# Jade_v1_schematics_PG3_PMIC_AXP192.net
KiCad netlist of a schematic drawn in Altium Designer
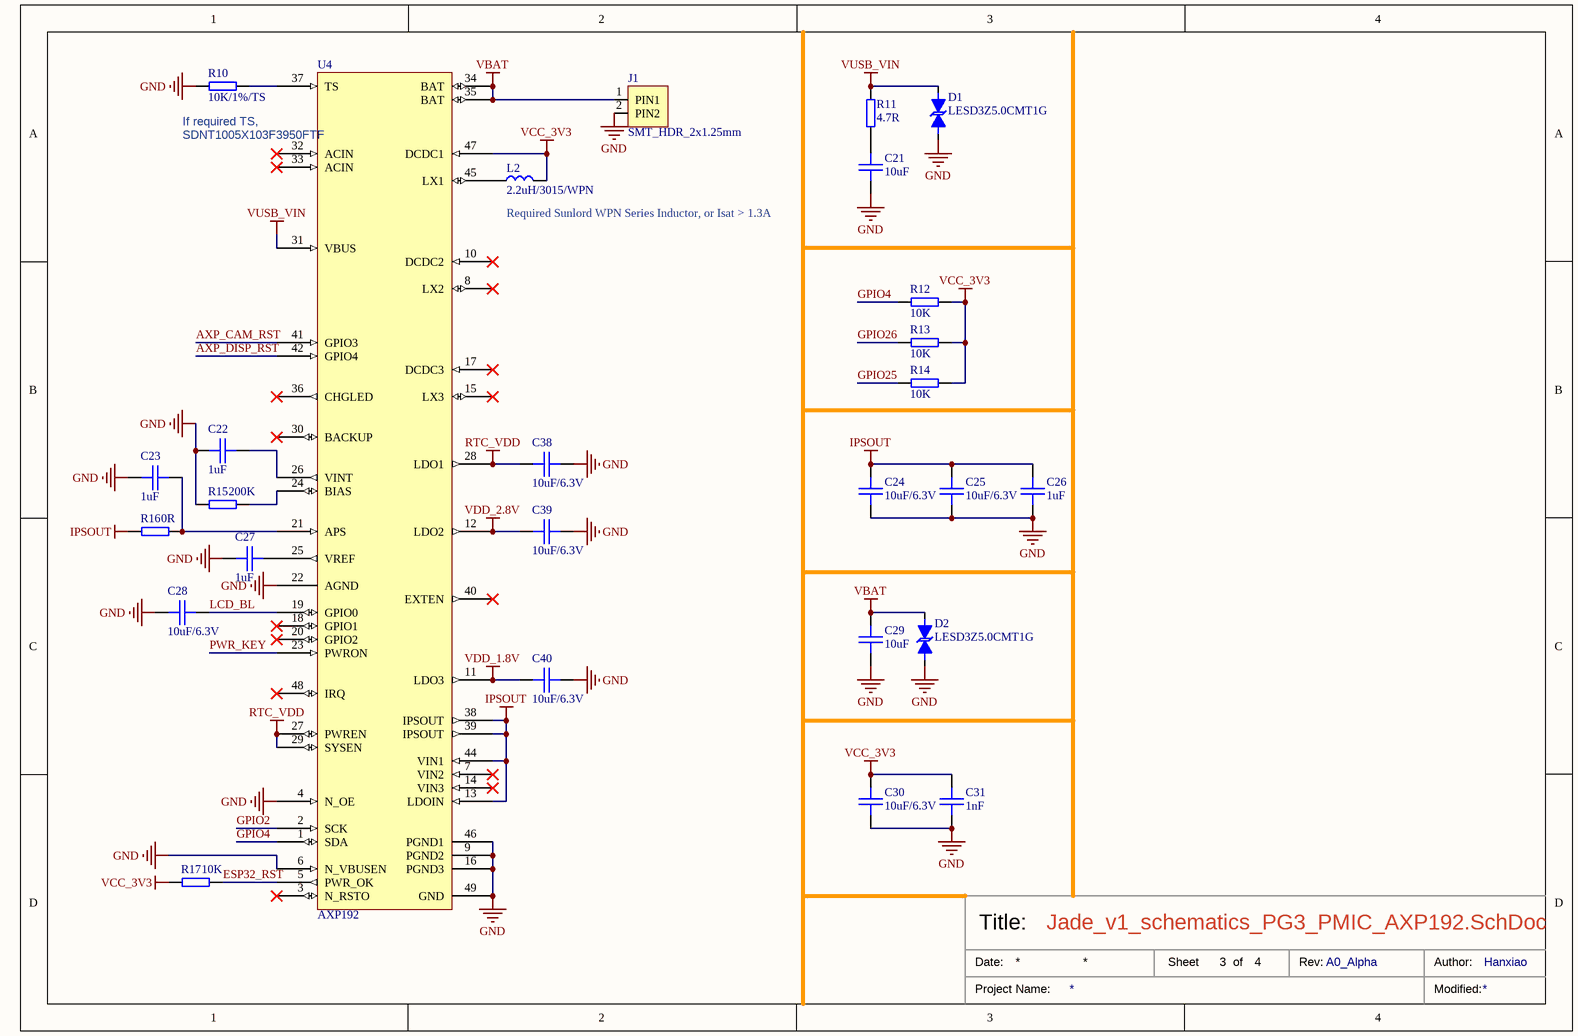
[diagram p0: Jade_v1_schematics_PG3_PMIC_AXP192.SchDoc]

(export (version "E")
  (design (tool "Eeschema 10.0.6"))
  (components
    (comp (ref "C21")
      (value "10uF")
      (footprint "SMT_C_0402")
      (description "Surface mount capacitor 0402")
      (libsource (lib "Vowstar_Basic_Device") (part "SMT_C_0402"))
    )
    (comp (ref "C22")
      (value "1uF")
      (footprint "SMT_C_0402")
      (description "Surface mount capacitor 0402")
      (libsource (lib "Vowstar_Basic_Device") (part "SMT_C_0402"))
    )
    (comp (ref "C23")
      (value "1uF")
      (footprint "SMT_C_0402")
      (description "Surface mount capacitor 0402")
      (libsource (lib "Vowstar_Basic_Device") (part "SMT_C_0402"))
    )
    (comp (ref "C24")
      (value "10uF/6.3V")
      (footprint "SMT_C_0603")
      (description "Surface mount capacitor 0603")
      (libsource (lib "Vowstar_Basic_Device") (part "SMT_C_0603"))
    )
    (comp (ref "C25")
      (value "10uF/6.3V")
      (footprint "SMT_C_0603")
      (description "Surface mount capacitor 0603")
      (libsource (lib "Vowstar_Basic_Device") (part "SMT_C_0603"))
    )
    (comp (ref "C26")
      (value "1uF")
      (footprint "SMT_C_0402")
      (description "Surface mount capacitor 0402")
      (libsource (lib "Vowstar_Basic_Device") (part "SMT_C_0402"))
    )
    (comp (ref "C27")
      (value "1uF")
      (footprint "SMT_C_0402")
      (description "Surface mount capacitor 0402")
      (libsource (lib "Vowstar_Basic_Device") (part "SMT_C_0402"))
    )
    (comp (ref "C28")
      (value "10uF/6.3V")
      (footprint "SMT_C_0603")
      (description "Surface mount capacitor 0603")
      (libsource (lib "Vowstar_Basic_Device") (part "SMT_C_0603"))
    )
    (comp (ref "C29")
      (value "10uF")
      (footprint "SMT_C_0402")
      (description "Surface mount capacitor 0402")
      (libsource (lib "Vowstar_Basic_Device") (part "SMT_C_0402"))
    )
    (comp (ref "C30")
      (value "10uF/6.3V")
      (footprint "SMT_C_0603")
      (description "Surface mount capacitor 0603")
      (libsource (lib "Vowstar_Basic_Device") (part "SMT_C_0603"))
    )
    (comp (ref "C31")
      (value "1nF")
      (footprint "SMT_C_0402")
      (description "Surface mount capacitor 0402")
      (libsource (lib "Vowstar_Basic_Device") (part "SMT_C_0402"))
    )
    (comp (ref "C38")
      (value "10uF/6.3V")
      (footprint "SMT_C_0603")
      (description "Surface mount capacitor 0603")
      (libsource (lib "Vowstar_Basic_Device") (part "SMT_C_0603"))
    )
    (comp (ref "C39")
      (value "10uF/6.3V")
      (footprint "SMT_C_0603")
      (description "Surface mount capacitor 0603")
      (libsource (lib "Vowstar_Basic_Device") (part "SMT_C_0603"))
    )
    (comp (ref "C40")
      (value "10uF/6.3V")
      (footprint "SMT_C_0603")
      (description "Surface mount capacitor 0603")
      (libsource (lib "Vowstar_Basic_Device") (part "SMT_C_0603"))
    )
    (comp (ref "D1")
      (value "LESD3Z5.0CMT1G")
      (footprint "SMT_DIODE_SOD_323")
      (description "Surface mount bidirectional TVS diode SOD-523(0603) Package")
      (libsource (lib "Vowstar_Basic_Device") (part "SMT_DIODE_TVS_B_SOD_523"))
    )
    (comp (ref "D2")
      (value "LESD3Z5.0CMT1G")
      (footprint "SMT_DIODE_SOD_323")
      (description "Surface mount bidirectional TVS diode SOD-523(0603) Package")
      (libsource (lib "Vowstar_Basic_Device") (part "SMT_DIODE_TVS_B_SOD_523"))
    )
    (comp (ref "J1")
      (value "SMT_HDR_2x1.25mm")
      (footprint "SMT_HDR_2x1.25mm")
      (description "Surface mount header 2x1.25mm")
      (libsource (lib "Vowstar_Connector") (part "SMT_HDR_2x1.25mm"))
    )
    (comp (ref "L2")
      (value "2.2uH/3015/WPN")
      (footprint "SMT_L_3.0mm")
      (description "SMT Power Inductor, 3.3x3.3x1mm")
      (libsource (lib "Vowstar_Basic_Device") (part "SMT_L_3.0mm"))
    )
    (comp (ref "R10")
      (value "10K/1%/TS")
      (footprint "SMT_R_0402")
      (description "Surface mount resistor 0402")
      (libsource (lib "Vowstar_Basic_Device") (part "SMT_R_0402"))
    )
    (comp (ref "R11")
      (value "4.7R")
      (footprint "SMT_R_0402")
      (description "Surface mount resistor 0402")
      (libsource (lib "Vowstar_Basic_Device") (part "SMT_R_0402"))
    )
    (comp (ref "R12")
      (value "10K")
      (footprint "SMT_R_0402")
      (description "Surface mount resistor 0402")
      (libsource (lib "Vowstar_Basic_Device") (part "SMT_R_0402"))
    )
    (comp (ref "R13")
      (value "10K")
      (footprint "SMT_R_0402")
      (description "Surface mount resistor 0402")
      (libsource (lib "Vowstar_Basic_Device") (part "SMT_R_0402"))
    )
    (comp (ref "R14")
      (value "10K")
      (footprint "SMT_R_0402")
      (description "Surface mount resistor 0402")
      (libsource (lib "Vowstar_Basic_Device") (part "SMT_R_0402"))
    )
    (comp (ref "R15")
      (value "200K")
      (footprint "SMT_R_0402")
      (description "Surface mount resistor 0402")
      (libsource (lib "Vowstar_Basic_Device") (part "SMT_R_0402"))
    )
    (comp (ref "R16")
      (value "0R")
      (footprint "SMT_R_0402")
      (description "Surface mount resistor 0402")
      (libsource (lib "Vowstar_Basic_Device") (part "SMT_R_0402"))
    )
    (comp (ref "R17")
      (value "10K")
      (footprint "SMT_R_0402")
      (description "Surface mount resistor 0402")
      (libsource (lib "Vowstar_Basic_Device") (part "SMT_R_0402"))
    )
    (comp (ref "U4")
      (value "AXP192")
      (footprint "PQFN40P600X600X90_HS-49N")
      (libsource (lib "LV-POWER-MAN") (part "AXP192"))
    )
  )
  (nets
    (net (code "1") (name "/AXP_CAM_RST") (class "Default")
      (node (ref "U4") (pin "41") (pinfunction "GPIO3_41") (pintype "input"))
    )
    (net (code "2") (name "/AXP_DISP_RST") (class "Default")
      (node (ref "U4") (pin "42") (pinfunction "GPIO4_42") (pintype "input"))
    )
    (net (code "3") (name "/ESP32_RST") (class "Default")
      (node (ref "R17") (pin "2") (pinfunction "2_2") (pintype "passive"))
      (node (ref "U4") (pin "5") (pinfunction "PWR_OK_5") (pintype "output"))
    )
    (net (code "4") (name "/GPIO2") (class "Default")
      (node (ref "U4") (pin "2") (pinfunction "SCK_2") (pintype "input"))
    )
    (net (code "5") (name "/GPIO4") (class "Default")
      (node (ref "R12") (pin "2") (pinfunction "2_2") (pintype "passive"))
      (node (ref "U4") (pin "1") (pinfunction "SDA_1") (pintype "bidirectional"))
    )
    (net (code "6") (name "/GPIO25") (class "Default")
      (node (ref "R14") (pin "2") (pinfunction "2_2") (pintype "passive"))
    )
    (net (code "7") (name "/GPIO26") (class "Default")
      (node (ref "R13") (pin "2") (pinfunction "2_2") (pintype "passive"))
    )
    (net (code "8") (name "/LCD_BL") (class "Default")
      (node (ref "C28") (pin "2") (pinfunction "2_2") (pintype "passive"))
      (node (ref "U4") (pin "19") (pinfunction "GPIO0_19") (pintype "bidirectional"))
    )
    (net (code "9") (name "/PWR_KEY") (class "Default")
      (node (ref "U4") (pin "23") (pinfunction "PWRON_23") (pintype "input"))
    )
    (net (code "10") (name "GND") (class "Default")
      (node (ref "C21") (pin "1") (pinfunction "1_1") (pintype "passive"))
      (node (ref "C22") (pin "1") (pinfunction "1_1") (pintype "passive"))
      (node (ref "C23") (pin "1") (pinfunction "1_1") (pintype "passive"))
      (node (ref "C24") (pin "1") (pinfunction "1_1") (pintype "passive"))
      (node (ref "C25") (pin "1") (pinfunction "1_1") (pintype "passive"))
      (node (ref "C26") (pin "1") (pinfunction "1_1") (pintype "passive"))
      (node (ref "C27") (pin "1") (pinfunction "1_1") (pintype "passive"))
      (node (ref "C28") (pin "1") (pinfunction "1_1") (pintype "passive"))
      (node (ref "C29") (pin "1") (pinfunction "1_1") (pintype "passive"))
      (node (ref "C30") (pin "1") (pinfunction "1_1") (pintype "passive"))
      (node (ref "C31") (pin "1") (pinfunction "1_1") (pintype "passive"))
      (node (ref "C38") (pin "1") (pinfunction "1_1") (pintype "passive"))
      (node (ref "C39") (pin "1") (pinfunction "1_1") (pintype "passive"))
      (node (ref "C40") (pin "1") (pinfunction "1_1") (pintype "passive"))
      (node (ref "D1") (pin "1") (pinfunction "A_1") (pintype "passive"))
      (node (ref "D2") (pin "1") (pinfunction "A_1") (pintype "passive"))
      (node (ref "J1") (pin "2") (pinfunction "PIN2_2") (pintype "passive"))
      (node (ref "R10") (pin "1") (pinfunction "1_1") (pintype "passive"))
      (node (ref "R15") (pin "1") (pinfunction "1_1") (pintype "passive"))
      (node (ref "U4") (pin "16") (pinfunction "PGND3_16") (pintype "power_in"))
      (node (ref "U4") (pin "22") (pinfunction "AGND_22") (pintype "power_in"))
      (node (ref "U4") (pin "4") (pinfunction "N_OE_4") (pintype "input"))
      (node (ref "U4") (pin "46") (pinfunction "PGND1_46") (pintype "power_in"))
      (node (ref "U4") (pin "49") (pinfunction "GND_49") (pintype "power_in"))
      (node (ref "U4") (pin "6") (pinfunction "N_VBUSEN_6") (pintype "input"))
      (node (ref "U4") (pin "9") (pinfunction "PGND2_9") (pintype "power_in"))
    )
    (net (code "11") (name "IPSOUT") (class "Default")
      (node (ref "C24") (pin "2") (pinfunction "2_2") (pintype "passive"))
      (node (ref "C25") (pin "2") (pinfunction "2_2") (pintype "passive"))
      (node (ref "C26") (pin "2") (pinfunction "2_2") (pintype "passive"))
      (node (ref "R16") (pin "1") (pinfunction "1_1") (pintype "passive"))
      (node (ref "U4") (pin "13") (pinfunction "LDOIN_13") (pintype "input"))
      (node (ref "U4") (pin "38") (pinfunction "IPSOUT_38") (pintype "output"))
      (node (ref "U4") (pin "39") (pinfunction "IPSOUT_39") (pintype "output"))
      (node (ref "U4") (pin "44") (pinfunction "VIN1_44") (pintype "input"))
    )
    (net (code "12") (name "Net-(C21-Pad2)") (class "Default")
      (node (ref "C21") (pin "2") (pinfunction "2_2") (pintype "passive"))
      (node (ref "R11") (pin "1") (pinfunction "1_1") (pintype "passive"))
    )
    (net (code "13") (name "Net-(U4-APS)") (class "Default")
      (node (ref "C23") (pin "2") (pinfunction "2_2") (pintype "passive"))
      (node (ref "R16") (pin "2") (pinfunction "2_2") (pintype "passive"))
      (node (ref "U4") (pin "21") (pinfunction "APS_21") (pintype "input"))
    )
    (net (code "14") (name "Net-(U4-BIAS)") (class "Default")
      (node (ref "R15") (pin "2") (pinfunction "2_2") (pintype "passive"))
      (node (ref "U4") (pin "24") (pinfunction "BIAS_24") (pintype "bidirectional"))
    )
    (net (code "15") (name "Net-(U4-LX1)") (class "Default")
      (node (ref "L2") (pin "2") (pinfunction "2_2") (pintype "passive"))
      (node (ref "U4") (pin "45") (pinfunction "LX1_45") (pintype "bidirectional"))
    )
    (net (code "16") (name "Net-(U4-TS)") (class "Default")
      (node (ref "R10") (pin "2") (pinfunction "2_2") (pintype "passive"))
      (node (ref "U4") (pin "37") (pinfunction "TS_37") (pintype "input"))
    )
    (net (code "17") (name "Net-(U4-VINT)") (class "Default")
      (node (ref "C22") (pin "2") (pinfunction "2_2") (pintype "passive"))
      (node (ref "U4") (pin "26") (pinfunction "VINT_26") (pintype "output"))
    )
    (net (code "18") (name "Net-(U4-VREF)") (class "Default")
      (node (ref "C27") (pin "2") (pinfunction "2_2") (pintype "passive"))
      (node (ref "U4") (pin "25") (pinfunction "VREF_25") (pintype "output"))
    )
    (net (code "19") (name "RTC_VDD") (class "Default")
      (node (ref "C38") (pin "2") (pinfunction "2_2") (pintype "passive"))
      (node (ref "U4") (pin "27") (pinfunction "PWREN_27") (pintype "bidirectional"))
      (node (ref "U4") (pin "28") (pinfunction "LDO1_28") (pintype "output"))
      (node (ref "U4") (pin "29") (pinfunction "SYSEN_29") (pintype "bidirectional"))
    )
    (net (code "20") (name "VBAT") (class "Default")
      (node (ref "C29") (pin "2") (pinfunction "2_2") (pintype "passive"))
      (node (ref "D2") (pin "2") (pinfunction "K_2") (pintype "passive"))
      (node (ref "J1") (pin "1") (pinfunction "PIN1_1") (pintype "passive"))
      (node (ref "U4") (pin "34") (pinfunction "BAT_34") (pintype "bidirectional"))
      (node (ref "U4") (pin "35") (pinfunction "BAT_35") (pintype "bidirectional"))
    )
    (net (code "21") (name "VCC_3V3") (class "Default")
      (node (ref "C30") (pin "2") (pinfunction "2_2") (pintype "passive"))
      (node (ref "C31") (pin "2") (pinfunction "2_2") (pintype "passive"))
      (node (ref "L2") (pin "1") (pinfunction "1_1") (pintype "passive"))
      (node (ref "R12") (pin "1") (pinfunction "1_1") (pintype "passive"))
      (node (ref "R13") (pin "1") (pinfunction "1_1") (pintype "passive"))
      (node (ref "R14") (pin "1") (pinfunction "1_1") (pintype "passive"))
      (node (ref "R17") (pin "1") (pinfunction "1_1") (pintype "passive"))
      (node (ref "U4") (pin "47") (pinfunction "DCDC1_47") (pintype "input"))
    )
    (net (code "22") (name "VDD_1.8V") (class "Default")
      (node (ref "C40") (pin "2") (pinfunction "2_2") (pintype "passive"))
      (node (ref "U4") (pin "11") (pinfunction "LDO3_11") (pintype "output"))
    )
    (net (code "23") (name "VDD_2.8V") (class "Default")
      (node (ref "C39") (pin "2") (pinfunction "2_2") (pintype "passive"))
      (node (ref "U4") (pin "12") (pinfunction "LDO2_12") (pintype "output"))
    )
    (net (code "24") (name "VUSB_VIN") (class "Default")
      (node (ref "D1") (pin "2") (pinfunction "K_2") (pintype "passive"))
      (node (ref "R11") (pin "2") (pinfunction "2_2") (pintype "passive"))
      (node (ref "U4") (pin "31") (pinfunction "VBUS_31") (pintype "input"))
    )
    (net (code "25") (name "unconnected-(U4-ACIN-Pad32)") (class "Default")
      (node (ref "U4") (pin "32") (pinfunction "ACIN_32") (pintype "input+no_connect"))
    )
    (net (code "26") (name "unconnected-(U4-ACIN-Pad33)") (class "Default")
      (node (ref "U4") (pin "33") (pinfunction "ACIN_33") (pintype "input+no_connect"))
    )
    (net (code "27") (name "unconnected-(U4-BACKUP-Pad30)") (class "Default")
      (node (ref "U4") (pin "30") (pinfunction "BACKUP_30") (pintype "bidirectional+no_connect"))
    )
    (net (code "28") (name "unconnected-(U4-CHGLED-Pad36)") (class "Default")
      (node (ref "U4") (pin "36") (pinfunction "CHGLED_36") (pintype "output+no_connect"))
    )
    (net (code "29") (name "unconnected-(U4-DCDC2-Pad10)") (class "Default")
      (node (ref "U4") (pin "10") (pinfunction "DCDC2_10") (pintype "input+no_connect"))
    )
    (net (code "30") (name "unconnected-(U4-DCDC3-Pad17)") (class "Default")
      (node (ref "U4") (pin "17") (pinfunction "DCDC3_17") (pintype "input+no_connect"))
    )
    (net (code "31") (name "unconnected-(U4-EXTEN-Pad40)") (class "Default")
      (node (ref "U4") (pin "40") (pinfunction "EXTEN_40") (pintype "output+no_connect"))
    )
    (net (code "32") (name "unconnected-(U4-GPIO1-Pad18)") (class "Default")
      (node (ref "U4") (pin "18") (pinfunction "GPIO1_18") (pintype "bidirectional+no_connect"))
    )
    (net (code "33") (name "unconnected-(U4-GPIO2-Pad20)") (class "Default")
      (node (ref "U4") (pin "20") (pinfunction "GPIO2_20") (pintype "bidirectional+no_connect"))
    )
    (net (code "34") (name "unconnected-(U4-IRQ-Pad48)") (class "Default")
      (node (ref "U4") (pin "48") (pinfunction "IRQ_48") (pintype "bidirectional+no_connect"))
    )
    (net (code "35") (name "unconnected-(U4-LX2-Pad8)") (class "Default")
      (node (ref "U4") (pin "8") (pinfunction "LX2_8") (pintype "bidirectional+no_connect"))
    )
    (net (code "36") (name "unconnected-(U4-LX3-Pad15)") (class "Default")
      (node (ref "U4") (pin "15") (pinfunction "LX3_15") (pintype "bidirectional+no_connect"))
    )
    (net (code "37") (name "unconnected-(U4-N_RSTO-Pad3)") (class "Default")
      (node (ref "U4") (pin "3") (pinfunction "N_RSTO_3") (pintype "bidirectional+no_connect"))
    )
    (net (code "38") (name "unconnected-(U4-VIN2-Pad7)") (class "Default")
      (node (ref "U4") (pin "7") (pinfunction "VIN2_7") (pintype "input+no_connect"))
    )
    (net (code "39") (name "unconnected-(U4-VIN3-Pad14)") (class "Default")
      (node (ref "U4") (pin "14") (pinfunction "VIN3_14") (pintype "input+no_connect"))
    )
  )
)
